# Adafruit_1_3_128x64_OLED.net
KiCad netlist of a schematic drawn in EAGLE
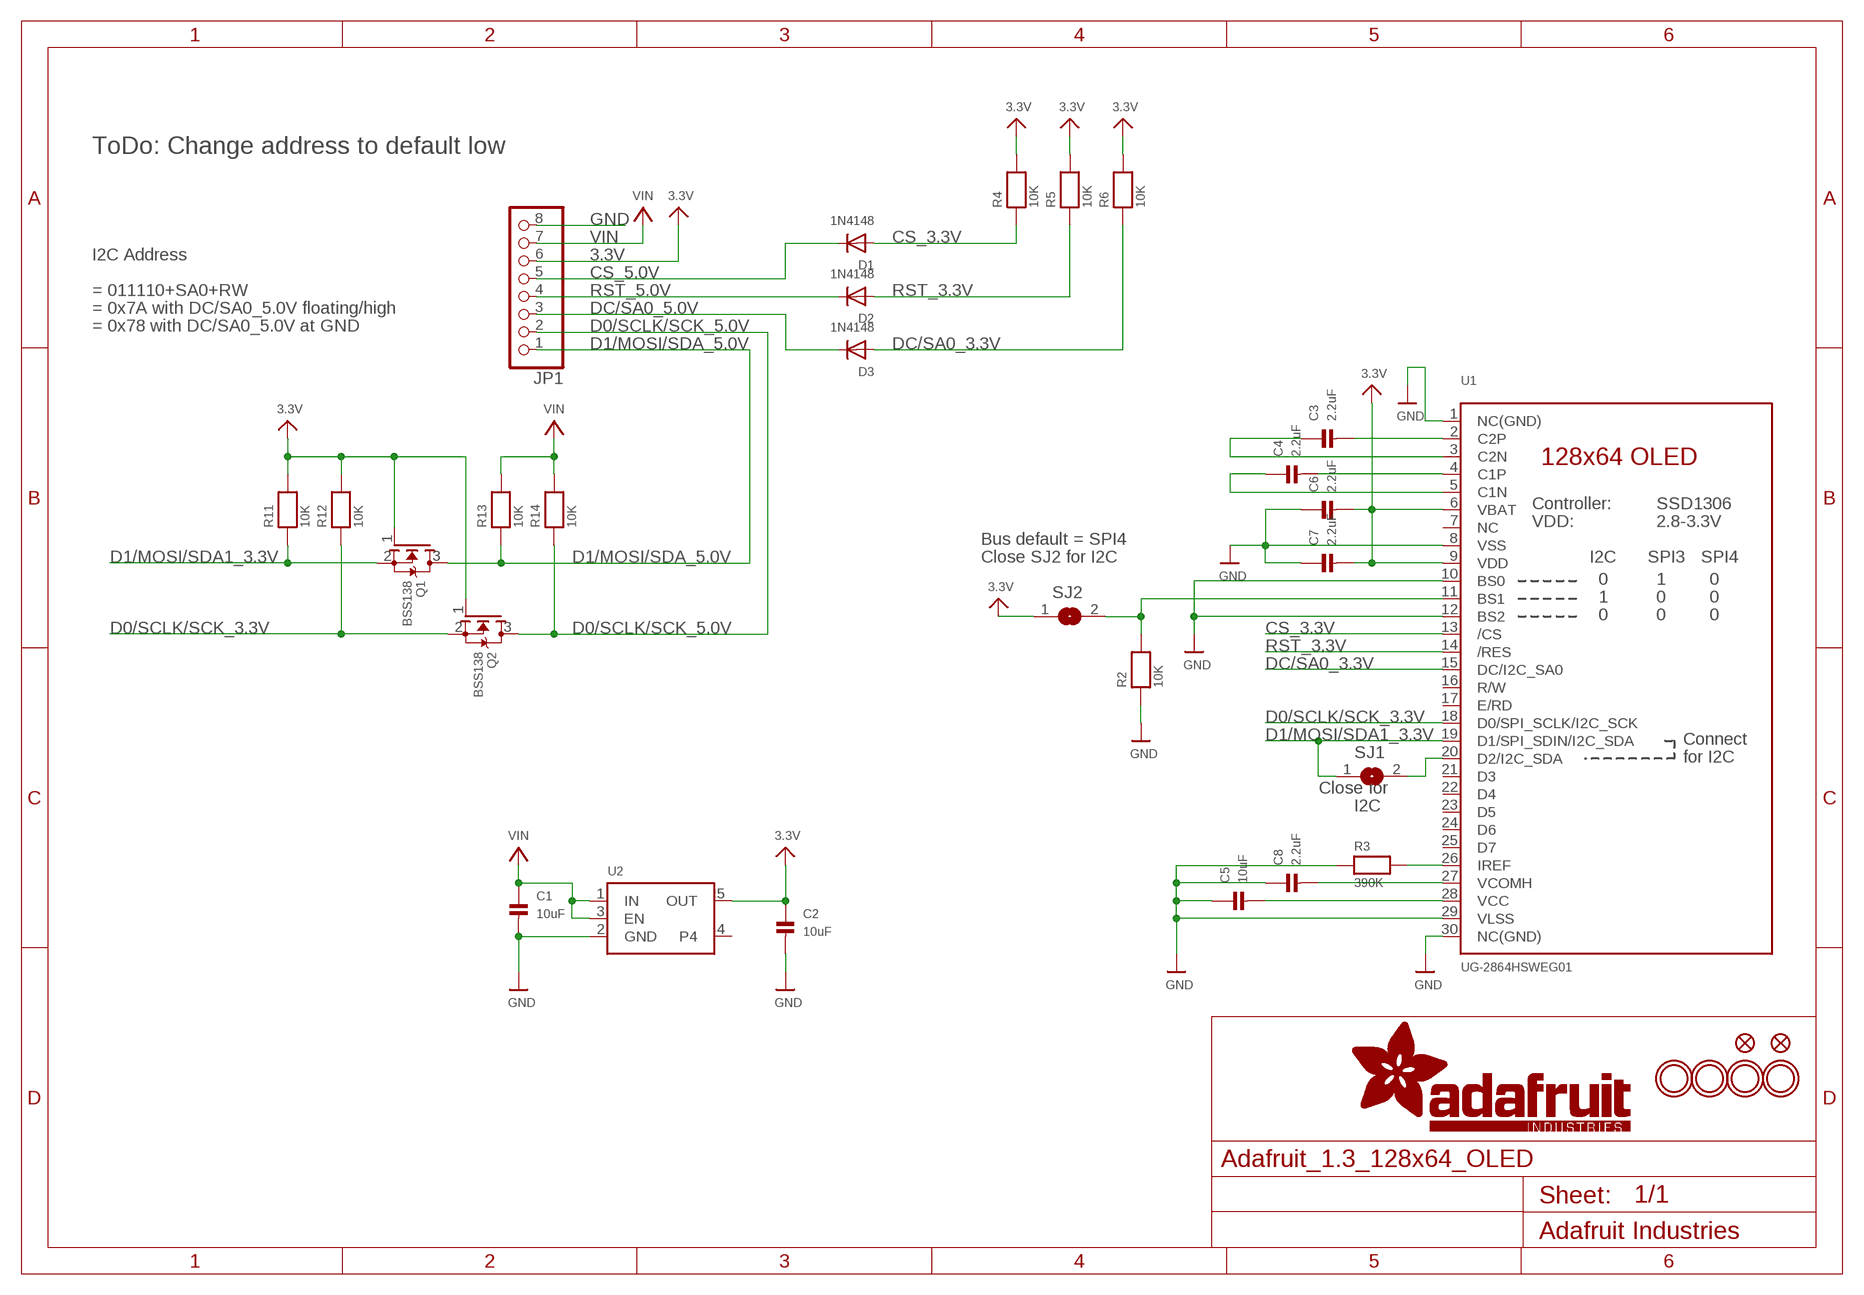
[diagram p0: schematic, sheet 1]

(export (version "E")
  (design (tool "Eeschema 10.0.6"))
  (components
    (comp (ref "C1")
      (value "10uF")
      (footprint "eagle-import:0805")
      (libsource (lib "eagle-import") (part "CAP_CERAMIC0805"))
    )
    (comp (ref "C2")
      (value "10uF")
      (footprint "eagle-import:0805")
      (libsource (lib "eagle-import") (part "CAP_CERAMIC0805"))
    )
    (comp (ref "C3")
      (value "2.2uF")
      (footprint "eagle-import:0805")
      (libsource (lib "eagle-import") (part "CAP_CERAMIC0805"))
    )
    (comp (ref "C4")
      (value "2.2uF")
      (footprint "eagle-import:0805")
      (libsource (lib "eagle-import") (part "CAP_CERAMIC0805"))
    )
    (comp (ref "C5")
      (value "10uF")
      (footprint "eagle-import:0805")
      (libsource (lib "eagle-import") (part "CAP_CERAMIC0805"))
    )
    (comp (ref "C6")
      (value "2.2uF")
      (footprint "eagle-import:0805")
      (libsource (lib "eagle-import") (part "CAP_CERAMIC0805"))
    )
    (comp (ref "C7")
      (value "2.2uF")
      (footprint "eagle-import:0805")
      (libsource (lib "eagle-import") (part "CAP_CERAMIC0805"))
    )
    (comp (ref "C8")
      (value "2.2uF")
      (footprint "eagle-import:0805")
      (libsource (lib "eagle-import") (part "CAP_CERAMIC0805"))
    )
    (comp (ref "D1")
      (value "1N4148")
      (footprint "eagle-import:SOD-323")
      (libsource (lib "eagle-import") (part "DIODESOD-323"))
    )
    (comp (ref "D2")
      (value "1N4148")
      (footprint "eagle-import:SOD-323")
      (libsource (lib "eagle-import") (part "DIODESOD-323"))
    )
    (comp (ref "D3")
      (value "1N4148")
      (footprint "eagle-import:SOD-323")
      (libsource (lib "eagle-import") (part "DIODESOD-323"))
    )
    (comp (ref "FID1")
      (value "FIDUCIAL\"\"")
      (footprint "eagle-import:FIDUCIAL_1MM")
      (libsource (lib "eagle-import") (part "FIDUCIAL{dblquote}{dblquote}"))
    )
    (comp (ref "FID2")
      (value "FIDUCIAL\"\"")
      (footprint "eagle-import:FIDUCIAL_1MM")
      (libsource (lib "eagle-import") (part "FIDUCIAL{dblquote}{dblquote}"))
    )
    (comp (ref "JP1")
      (value "HEADER-1X870MIL")
      (footprint "eagle-import:1X08_ROUND_70")
      (libsource (lib "eagle-import") (part "HEADER-1X870MIL"))
    )
    (comp (ref "Q1")
      (value "BSS138")
      (footprint "eagle-import:SOT23-WIDE")
      (libsource (lib "eagle-import") (part "MOSFET-NWIDE"))
    )
    (comp (ref "Q2")
      (value "BSS138")
      (footprint "eagle-import:SOT23-WIDE")
      (libsource (lib "eagle-import") (part "MOSFET-NWIDE"))
    )
    (comp (ref "R2")
      (value "10K")
      (footprint "eagle-import:0805")
      (libsource (lib "eagle-import") (part "RESISTOR0805"))
    )
    (comp (ref "R3")
      (value "390K")
      (footprint "eagle-import:0805")
      (libsource (lib "eagle-import") (part "RESISTOR0805"))
    )
    (comp (ref "R4")
      (value "10K")
      (footprint "eagle-import:0805")
      (libsource (lib "eagle-import") (part "RESISTOR0805"))
    )
    (comp (ref "R5")
      (value "10K")
      (footprint "eagle-import:0805")
      (libsource (lib "eagle-import") (part "RESISTOR0805"))
    )
    (comp (ref "R6")
      (value "10K")
      (footprint "eagle-import:0805")
      (libsource (lib "eagle-import") (part "RESISTOR0805"))
    )
    (comp (ref "R11")
      (value "10K")
      (footprint "eagle-import:0805")
      (libsource (lib "eagle-import") (part "RESISTOR0805"))
    )
    (comp (ref "R12")
      (value "10K")
      (footprint "eagle-import:0805")
      (libsource (lib "eagle-import") (part "RESISTOR0805"))
    )
    (comp (ref "R13")
      (value "10K")
      (footprint "eagle-import:0805")
      (libsource (lib "eagle-import") (part "RESISTOR0805"))
    )
    (comp (ref "R14")
      (value "10K")
      (footprint "eagle-import:0805")
      (libsource (lib "eagle-import") (part "RESISTOR0805"))
    )
    (comp (ref "SJ1")
      (value "SOLDERJUMPERREFLOW_NOPASTE")
      (footprint "eagle-import:SOLDERJUMPER_REFLOW_NOPASTE")
      (libsource (lib "eagle-import") (part "SOLDERJUMPERREFLOW_NOPASTE"))
    )
    (comp (ref "SJ2")
      (value "SOLDERJUMPERREFLOW_NOPASTE")
      (footprint "eagle-import:SOLDERJUMPER_REFLOW_NOPASTE")
      (libsource (lib "eagle-import") (part "SOLDERJUMPERREFLOW_NOPASTE"))
    )
    (comp (ref "U$23")
      (value "MOUNTINGHOLE2.5")
      (footprint "eagle-import:MOUNTINGHOLE_2.5_PLATED")
      (libsource (lib "eagle-import") (part "MOUNTINGHOLE2.5"))
    )
    (comp (ref "U$24")
      (value "MOUNTINGHOLE2.5")
      (footprint "eagle-import:MOUNTINGHOLE_2.5_PLATED")
      (libsource (lib "eagle-import") (part "MOUNTINGHOLE2.5"))
    )
    (comp (ref "U$25")
      (value "MOUNTINGHOLE2.5")
      (footprint "eagle-import:MOUNTINGHOLE_2.5_PLATED")
      (libsource (lib "eagle-import") (part "MOUNTINGHOLE2.5"))
    )
    (comp (ref "U$26")
      (value "MOUNTINGHOLE2.5")
      (footprint "eagle-import:MOUNTINGHOLE_2.5_PLATED")
      (libsource (lib "eagle-import") (part "MOUNTINGHOLE2.5"))
    )
    (comp (ref "U1")
      (value "UG-2864HSWEG01")
      (footprint "eagle-import:UG-2864HSWEG01_1.3_WRAPAROUND")
      (libsource (lib "eagle-import") (part "DISP_OLED_UG-2864HSWEG01"))
    )
    (comp (ref "U2")
      (value "VREG_SOT23-5")
      (footprint "eagle-import:SOT23-5")
      (libsource (lib "eagle-import") (part "VREG_SOT23-5"))
    )
  )
  (nets
    (net (code "1") (name "/CS_3.3V") (class "Default")
      (node (ref "D1") (pin "A") (pinfunction "A_A") (pintype "passive"))
      (node (ref "R4") (pin "1") (pinfunction "1_1") (pintype "passive"))
      (node (ref "U1") (pin "13") (pinfunction "/CS_13") (pintype "input"))
    )
    (net (code "2") (name "/CS_5.0V") (class "Default")
      (node (ref "D1") (pin "C") (pinfunction "C_C") (pintype "passive"))
      (node (ref "JP1") (pin "5") (pinfunction "5_5") (pintype "passive"))
    )
    (net (code "3") (name "/D0{slash}SCLK{slash}SCK_3.3V") (class "Default")
      (node (ref "Q2") (pin "2") (pinfunction "S_2") (pintype "bidirectional"))
      (node (ref "R12") (pin "1") (pinfunction "1_1") (pintype "passive"))
      (node (ref "U1") (pin "18") (pinfunction "D0/SPI_SCLK/I2C_SCK_18") (pintype "bidirectional"))
    )
    (net (code "4") (name "/D0{slash}SCLK{slash}SCK_5.0V") (class "Default")
      (node (ref "JP1") (pin "2") (pinfunction "2_2") (pintype "passive"))
      (node (ref "Q2") (pin "3") (pinfunction "D_3") (pintype "bidirectional"))
      (node (ref "R14") (pin "1") (pinfunction "1_1") (pintype "passive"))
    )
    (net (code "5") (name "/D1{slash}MOSI{slash}SDA1_3.3V") (class "Default")
      (node (ref "Q1") (pin "2") (pinfunction "S_2") (pintype "bidirectional"))
      (node (ref "R11") (pin "1") (pinfunction "1_1") (pintype "passive"))
      (node (ref "SJ1") (pin "1") (pinfunction "1_1") (pintype "passive"))
      (node (ref "U1") (pin "19") (pinfunction "D1/SPI_SDIN/I2C_SDA_19") (pintype "bidirectional"))
    )
    (net (code "6") (name "/D1{slash}MOSI{slash}SDA_5.0V") (class "Default")
      (node (ref "JP1") (pin "1") (pinfunction "1_1") (pintype "passive"))
      (node (ref "Q1") (pin "3") (pinfunction "D_3") (pintype "bidirectional"))
      (node (ref "R13") (pin "1") (pinfunction "1_1") (pintype "passive"))
    )
    (net (code "7") (name "/DC{slash}SA0_3.3V") (class "Default")
      (node (ref "D3") (pin "A") (pinfunction "A_A") (pintype "passive"))
      (node (ref "R6") (pin "1") (pinfunction "1_1") (pintype "passive"))
      (node (ref "U1") (pin "15") (pinfunction "DC/I2C_SA0_15") (pintype "input"))
    )
    (net (code "8") (name "/DC{slash}SA0_5.0V") (class "Default")
      (node (ref "D3") (pin "C") (pinfunction "C_C") (pintype "passive"))
      (node (ref "JP1") (pin "3") (pinfunction "3_3") (pintype "passive"))
    )
    (net (code "9") (name "/RST_3.3V") (class "Default")
      (node (ref "D2") (pin "A") (pinfunction "A_A") (pintype "passive"))
      (node (ref "R5") (pin "1") (pinfunction "1_1") (pintype "passive"))
      (node (ref "U1") (pin "14") (pinfunction "/RES_14") (pintype "input"))
    )
    (net (code "10") (name "/RST_5.0V") (class "Default")
      (node (ref "D2") (pin "C") (pinfunction "C_C") (pintype "passive"))
      (node (ref "JP1") (pin "4") (pinfunction "4_4") (pintype "passive"))
    )
    (net (code "11") (name "3.3V") (class "Default")
      (node (ref "C2") (pin "1") (pinfunction "P$1_1") (pintype "passive"))
      (node (ref "C6") (pin "2") (pinfunction "P$2_2") (pintype "passive"))
      (node (ref "C7") (pin "2") (pinfunction "P$2_2") (pintype "passive"))
      (node (ref "JP1") (pin "6") (pinfunction "6_6") (pintype "passive"))
      (node (ref "Q1") (pin "1") (pinfunction "G_1") (pintype "bidirectional"))
      (node (ref "Q2") (pin "1") (pinfunction "G_1") (pintype "bidirectional"))
      (node (ref "R11") (pin "2") (pinfunction "2_2") (pintype "passive"))
      (node (ref "R12") (pin "2") (pinfunction "2_2") (pintype "passive"))
      (node (ref "R4") (pin "2") (pinfunction "2_2") (pintype "passive"))
      (node (ref "R5") (pin "2") (pinfunction "2_2") (pintype "passive"))
      (node (ref "R6") (pin "2") (pinfunction "2_2") (pintype "passive"))
      (node (ref "SJ2") (pin "1") (pinfunction "1_1") (pintype "passive"))
      (node (ref "U1") (pin "6") (pinfunction "VBAT_6") (pintype "input"))
      (node (ref "U1") (pin "9") (pinfunction "VDD_9") (pintype "power_in"))
      (node (ref "U2") (pin "5") (pinfunction "OUT_5") (pintype "bidirectional"))
    )
    (net (code "12") (name "GND") (class "Default")
      (node (ref "C1") (pin "2") (pinfunction "P$2_2") (pintype "passive"))
      (node (ref "C2") (pin "2") (pinfunction "P$2_2") (pintype "passive"))
      (node (ref "C5") (pin "1") (pinfunction "P$1_1") (pintype "passive"))
      (node (ref "C6") (pin "1") (pinfunction "P$1_1") (pintype "passive"))
      (node (ref "C7") (pin "1") (pinfunction "P$1_1") (pintype "passive"))
      (node (ref "C8") (pin "1") (pinfunction "P$1_1") (pintype "passive"))
      (node (ref "JP1") (pin "8") (pinfunction "8_8") (pintype "passive"))
      (node (ref "R2") (pin "1") (pinfunction "1_1") (pintype "passive"))
      (node (ref "R3") (pin "1") (pinfunction "1_1") (pintype "passive"))
      (node (ref "U1") (pin "1") (pinfunction "NC(GND)_1") (pintype "input"))
      (node (ref "U1") (pin "10") (pinfunction "BS0_10") (pintype "input"))
      (node (ref "U1") (pin "12") (pinfunction "BS2_12") (pintype "input"))
      (node (ref "U1") (pin "29") (pinfunction "VLSS_29") (pintype "power_in"))
      (node (ref "U1") (pin "30") (pinfunction "NC(GND)_30") (pintype "input"))
      (node (ref "U1") (pin "8") (pinfunction "VSS_8") (pintype "power_in"))
      (node (ref "U2") (pin "2") (pinfunction "GND_2") (pintype "bidirectional"))
    )
    (net (code "13") (name "Net-(C3-P$1)") (class "Default")
      (node (ref "C3") (pin "1") (pinfunction "P$1_1") (pintype "passive"))
      (node (ref "U1") (pin "3") (pinfunction "C2N_3") (pintype "input"))
    )
    (net (code "14") (name "Net-(C3-P$2)") (class "Default")
      (node (ref "C3") (pin "2") (pinfunction "P$2_2") (pintype "passive"))
      (node (ref "U1") (pin "2") (pinfunction "C2P_2") (pintype "input"))
    )
    (net (code "15") (name "Net-(C4-P$1)") (class "Default")
      (node (ref "C4") (pin "1") (pinfunction "P$1_1") (pintype "passive"))
      (node (ref "U1") (pin "5") (pinfunction "C1N_5") (pintype "input"))
    )
    (net (code "16") (name "Net-(C4-P$2)") (class "Default")
      (node (ref "C4") (pin "2") (pinfunction "P$2_2") (pintype "passive"))
      (node (ref "U1") (pin "4") (pinfunction "C1P_4") (pintype "input"))
    )
    (net (code "17") (name "Net-(C5-P$2)") (class "Default")
      (node (ref "C5") (pin "2") (pinfunction "P$2_2") (pintype "passive"))
      (node (ref "U1") (pin "28") (pinfunction "VCC_28") (pintype "power_in"))
    )
    (net (code "18") (name "Net-(C8-P$2)") (class "Default")
      (node (ref "C8") (pin "2") (pinfunction "P$2_2") (pintype "passive"))
      (node (ref "U1") (pin "27") (pinfunction "VCOMH_27") (pintype "output"))
    )
    (net (code "19") (name "Net-(U1-BS1)") (class "Default")
      (node (ref "R2") (pin "2") (pinfunction "2_2") (pintype "passive"))
      (node (ref "SJ2") (pin "2") (pinfunction "2_2") (pintype "passive"))
      (node (ref "U1") (pin "11") (pinfunction "BS1_11") (pintype "input"))
    )
    (net (code "20") (name "Net-(U1-D2{slash}I2C_SDA)") (class "Default")
      (node (ref "SJ1") (pin "2") (pinfunction "2_2") (pintype "passive"))
      (node (ref "U1") (pin "20") (pinfunction "D2/I2C_SDA_20") (pintype "bidirectional"))
    )
    (net (code "21") (name "Net-(U1-IREF)") (class "Default")
      (node (ref "R3") (pin "2") (pinfunction "2_2") (pintype "passive"))
      (node (ref "U1") (pin "26") (pinfunction "IREF_26") (pintype "input"))
    )
    (net (code "22") (name "VIN") (class "Default")
      (node (ref "C1") (pin "1") (pinfunction "P$1_1") (pintype "passive"))
      (node (ref "JP1") (pin "7") (pinfunction "7_7") (pintype "passive"))
      (node (ref "R13") (pin "2") (pinfunction "2_2") (pintype "passive"))
      (node (ref "R14") (pin "2") (pinfunction "2_2") (pintype "passive"))
      (node (ref "U2") (pin "1") (pinfunction "IN_1") (pintype "bidirectional"))
      (node (ref "U2") (pin "3") (pinfunction "EN_3") (pintype "bidirectional"))
    )
    (net (code "23") (name "unconnected-(U1-D3-Pad21)") (class "Default")
      (node (ref "U1") (pin "21") (pinfunction "D3_21") (pintype "bidirectional"))
    )
    (net (code "24") (name "unconnected-(U1-D4-Pad22)") (class "Default")
      (node (ref "U1") (pin "22") (pinfunction "D4_22") (pintype "bidirectional"))
    )
    (net (code "25") (name "unconnected-(U1-D5-Pad23)") (class "Default")
      (node (ref "U1") (pin "23") (pinfunction "D5_23") (pintype "bidirectional"))
    )
    (net (code "26") (name "unconnected-(U1-D6-Pad24)") (class "Default")
      (node (ref "U1") (pin "24") (pinfunction "D6_24") (pintype "bidirectional"))
    )
    (net (code "27") (name "unconnected-(U1-D7-Pad25)") (class "Default")
      (node (ref "U1") (pin "25") (pinfunction "D7_25") (pintype "bidirectional"))
    )
    (net (code "28") (name "unconnected-(U1-E{slash}RD-Pad17)") (class "Default")
      (node (ref "U1") (pin "17") (pinfunction "E/RD_17") (pintype "input"))
    )
    (net (code "29") (name "unconnected-(U1-NC-Pad7)") (class "Default")
      (node (ref "U1") (pin "7") (pinfunction "NC_7") (pintype "no_connect"))
    )
    (net (code "30") (name "unconnected-(U1-R{slash}W-Pad16)") (class "Default")
      (node (ref "U1") (pin "16") (pinfunction "R/W_16") (pintype "input"))
    )
    (net (code "31") (name "unconnected-(U2-P4-Pad4)") (class "Default")
      (node (ref "U2") (pin "4") (pinfunction "P4_4") (pintype "bidirectional"))
    )
  )
)
